# STM32-Mentor.net
KiCad netlist of a schematic drawn in Altium Designer
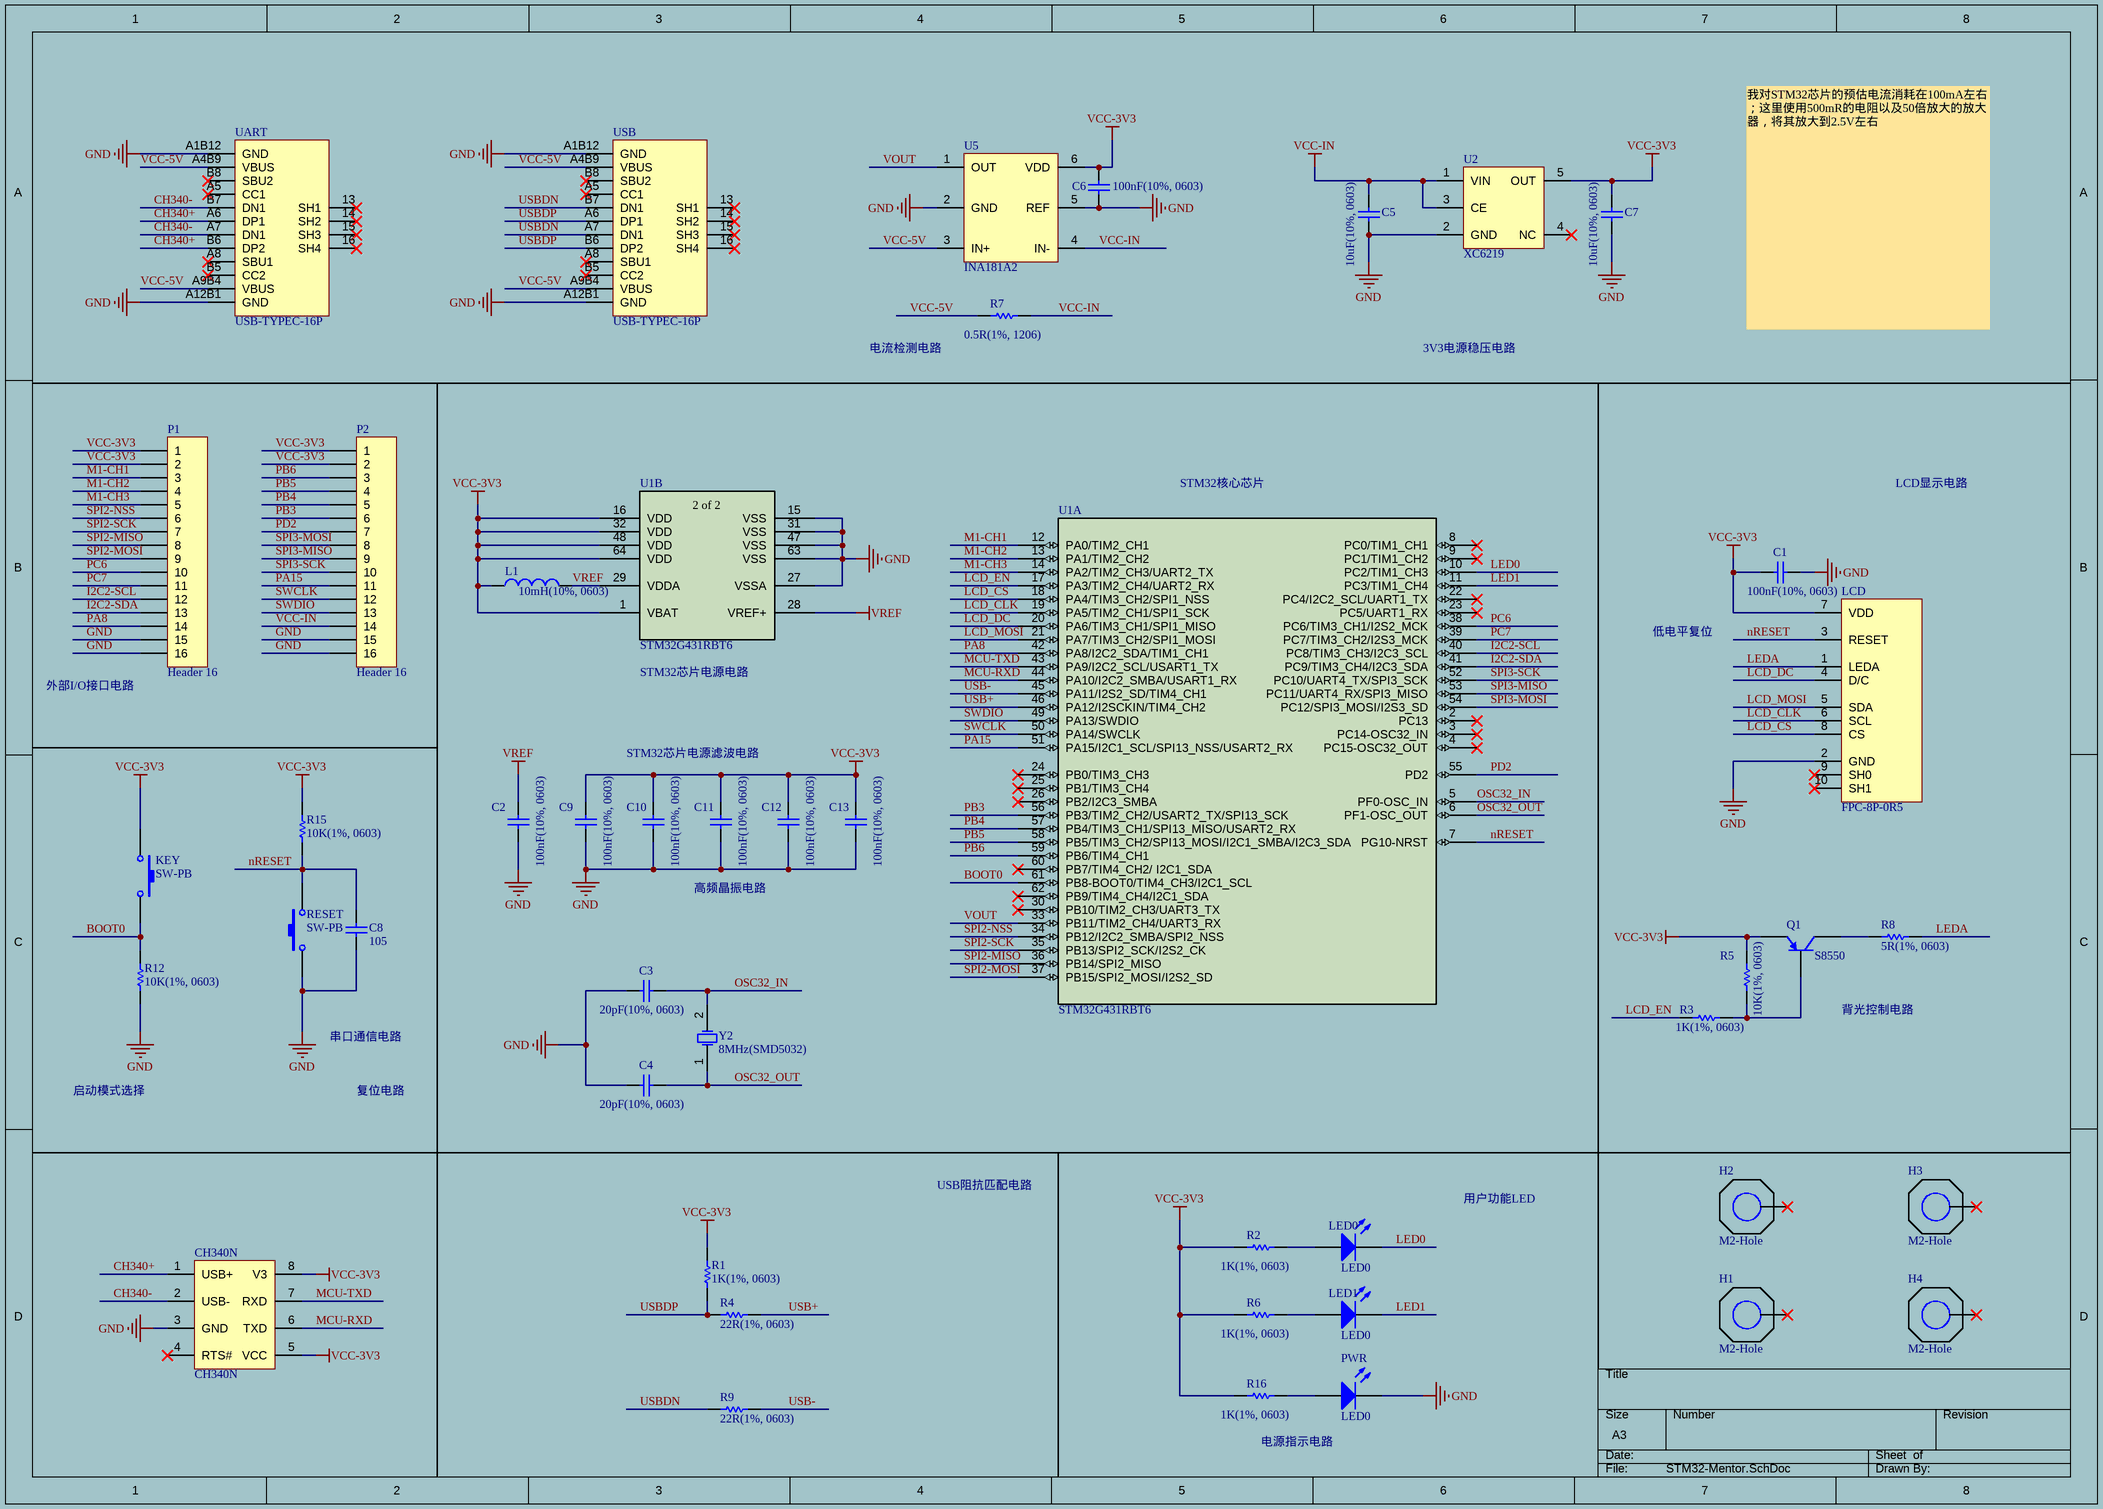
[diagram p0: STM32-Mentor.SchDoc]

(export (version "E")
  (design (tool "Eeschema 10.0.6"))
  (components
    (comp (ref "C1")
      (value "100nF(10%, 0603)")
      (footprint "0603C")
      (description "Capacitor")
      (fields (field (name "PUBLISHER") "Altium Limited"))
      (libsource (lib "Miscellaneous Devices") (part "Cap"))
    )
    (comp (ref "C2")
      (value "100nF(10%, 0603)")
      (footprint "0603C")
      (description "Capacitor")
      (fields (field (name "PUBLISHER") "Altium Limited"))
      (libsource (lib "Miscellaneous Devices") (part "Cap"))
    )
    (comp (ref "C3")
      (value "20pF(10%, 0603)")
      (footprint "0603C")
      (description "Capacitor")
      (fields (field (name "PUBLISHER") "Altium Limited"))
      (libsource (lib "Miscellaneous Devices") (part "Cap"))
    )
    (comp (ref "C4")
      (value "20pF(10%, 0603)")
      (footprint "0603C")
      (description "Capacitor")
      (fields (field (name "PUBLISHER") "Altium Limited"))
      (libsource (lib "Miscellaneous Devices") (part "Cap"))
    )
    (comp (ref "C5")
      (value "10uF(10%, 0603)")
      (footprint "0603C")
      (description "Capacitor")
      (fields (field (name "PUBLISHER") "Altium Limited"))
      (libsource (lib "Miscellaneous Devices") (part "Cap"))
    )
    (comp (ref "C6")
      (value "100nF(10%, 0603)")
      (footprint "0603C")
      (description "Capacitor")
      (fields (field (name "PUBLISHER") "Altium Limited"))
      (libsource (lib "Miscellaneous Devices") (part "Cap"))
    )
    (comp (ref "C7")
      (value "10uF(10%, 0603)")
      (footprint "0603C")
      (description "Capacitor")
      (fields (field (name "PUBLISHER") "Altium Limited"))
      (libsource (lib "Miscellaneous Devices") (part "Cap"))
    )
    (comp (ref "C8")
      (value "105")
      (footprint "0603C")
      (description "Capacitor")
      (fields (field (name "PUBLISHER") "Altium Limited"))
      (libsource (lib "Miscellaneous Devices") (part "Cap"))
    )
    (comp (ref "C9")
      (value "100nF(10%, 0603)")
      (footprint "0603C")
      (description "Capacitor")
      (fields (field (name "PUBLISHER") "Altium Limited"))
      (libsource (lib "Miscellaneous Devices") (part "Cap"))
    )
    (comp (ref "C10")
      (value "100nF(10%, 0603)")
      (footprint "0603C")
      (description "Capacitor")
      (fields (field (name "PUBLISHER") "Altium Limited"))
      (libsource (lib "Miscellaneous Devices") (part "Cap"))
    )
    (comp (ref "C11")
      (value "100nF(10%, 0603)")
      (footprint "0603C")
      (description "Capacitor")
      (fields (field (name "PUBLISHER") "Altium Limited"))
      (libsource (lib "Miscellaneous Devices") (part "Cap"))
    )
    (comp (ref "C12")
      (value "100nF(10%, 0603)")
      (footprint "0603C")
      (description "Capacitor")
      (fields (field (name "PUBLISHER") "Altium Limited"))
      (libsource (lib "Miscellaneous Devices") (part "Cap"))
    )
    (comp (ref "C13")
      (value "100nF(10%, 0603)")
      (footprint "0603C")
      (description "Capacitor")
      (fields (field (name "PUBLISHER") "Altium Limited"))
      (libsource (lib "Miscellaneous Devices") (part "Cap"))
    )
    (comp (ref "CH340N")
      (value "CH340N")
      (footprint "SOP8")
      (description "UART To USB")
      (libsource (lib "RegularLib") (part "CH340N"))
    )
    (comp (ref "H1") (value "M2-Hole") (footprint "M2-Hole") (libsource (lib "RegularLib") (part "M2-Hole")))
    (comp (ref "H2") (value "M2-Hole") (footprint "M2-Hole") (libsource (lib "RegularLib") (part "M2-Hole")))
    (comp (ref "H3") (value "M2-Hole") (footprint "M2-Hole") (libsource (lib "RegularLib") (part "M2-Hole")))
    (comp (ref "H4") (value "M2-Hole") (footprint "M2-Hole") (libsource (lib "RegularLib") (part "M2-Hole")))
    (comp (ref "KEY")
      (value "SW-PB")
      (footprint "SW2-4R2X3R4")
      (description "Switch")
      (fields (field (name "PUBLISHER") "Altium Limited"))
      (libsource (lib "Miscellaneous Devices") (part "SW-PB"))
    )
    (comp (ref "L1")
      (value "10mH(10%, 0603)")
      (footprint "0805L")
      (description "Inductor")
      (fields (field (name "PUBLISHER") "Altium Limited"))
      (libsource (lib "Miscellaneous Devices") (part "Inductor"))
    )
    (comp (ref "LCD")
      (value "FPC-8P-0R5")
      (footprint "FPC-8P-0R5")
      (libsource (lib "RegularLib") (part "FPC-8P-0R5"))
    )
    (comp (ref "LED0")
      (value "LED0")
      (footprint "LED-0805")
      (description "Typical INFRARED GaAs LED")
      (fields (field (name "PUBLISHER") "Altium Limited"))
      (libsource (lib "Miscellaneous Devices") (part "LED0"))
    )
    (comp (ref "LED1")
      (value "LED0")
      (footprint "LED-0805")
      (description "Typical INFRARED GaAs LED")
      (fields (field (name "PUBLISHER") "Altium Limited"))
      (libsource (lib "Miscellaneous Devices") (part "LED0"))
    )
    (comp (ref "P1")
      (value "Header 16")
      (footprint "HDR1X16")
      (description "Header, 16-Pin")
      (fields (field (name "PUBLISHER") "Altium Limited"))
      (libsource (lib "Miscellaneous Connectors") (part "Header 16"))
    )
    (comp (ref "P2")
      (value "Header 16")
      (footprint "HDR1X16")
      (description "Header, 16-Pin")
      (fields (field (name "PUBLISHER") "Altium Limited"))
      (libsource (lib "Miscellaneous Connectors") (part "Header 16"))
    )
    (comp (ref "PWR")
      (value "LED0")
      (footprint "LED-0805")
      (description "Typical INFRARED GaAs LED")
      (fields (field (name "PUBLISHER") "Altium Limited"))
      (libsource (lib "Miscellaneous Devices") (part "LED0"))
    )
    (comp (ref "Q1")
      (value "S8550")
      (footprint "SOT-23B_N")
      (description "PNP Bipolar Transistor")
      (fields (field (name "PUBLISHER") "Altium Limited"))
      (libsource (lib "Miscellaneous Devices") (part "PNP"))
    )
    (comp (ref "R1")
      (value "1K(1%, 0603)")
      (footprint "0603R")
      (description "Resistor")
      (fields (field (name "PUBLISHER") "Altium Limited"))
      (libsource (lib "Miscellaneous Devices") (part "Res1"))
    )
    (comp (ref "R2")
      (value "1K(1%, 0603)")
      (footprint "0603R")
      (description "Resistor")
      (fields (field (name "PUBLISHER") "Altium Limited"))
      (libsource (lib "Miscellaneous Devices") (part "Res1"))
    )
    (comp (ref "R3")
      (value "1K(1%, 0603)")
      (footprint "0603R")
      (description "Resistor")
      (fields (field (name "PUBLISHER") "Altium Limited"))
      (libsource (lib "Miscellaneous Devices") (part "Res1"))
    )
    (comp (ref "R4")
      (value "22R(1%, 0603)")
      (footprint "0603R")
      (description "Resistor")
      (fields (field (name "PUBLISHER") "Altium Limited"))
      (libsource (lib "Miscellaneous Devices") (part "Res1"))
    )
    (comp (ref "R5")
      (value "10K(1%, 0603)")
      (footprint "0603R")
      (description "Resistor")
      (fields (field (name "PUBLISHER") "Altium Limited"))
      (libsource (lib "Miscellaneous Devices") (part "Res1"))
    )
    (comp (ref "R6")
      (value "1K(1%, 0603)")
      (footprint "0603R")
      (description "Resistor")
      (fields (field (name "PUBLISHER") "Altium Limited"))
      (libsource (lib "Miscellaneous Devices") (part "Res1"))
    )
    (comp (ref "R7")
      (value "0.5R(1%, 1206)")
      (footprint "1206R")
      (description "Resistor")
      (fields (field (name "PUBLISHER") "Altium Limited"))
      (libsource (lib "Miscellaneous Devices") (part "Res1"))
    )
    (comp (ref "R8")
      (value "5R(1%, 0603)")
      (footprint "0603R")
      (description "Resistor")
      (fields (field (name "PUBLISHER") "Altium Limited"))
      (libsource (lib "Miscellaneous Devices") (part "Res1"))
    )
    (comp (ref "R9")
      (value "22R(1%, 0603)")
      (footprint "0603R")
      (description "Resistor")
      (fields (field (name "PUBLISHER") "Altium Limited"))
      (libsource (lib "Miscellaneous Devices") (part "Res1"))
    )
    (comp (ref "R12")
      (value "10K(1%, 0603)")
      (footprint "0603R")
      (description "Resistor")
      (fields (field (name "PUBLISHER") "Altium Limited"))
      (libsource (lib "Miscellaneous Devices") (part "Res1"))
    )
    (comp (ref "R15")
      (value "10K(1%, 0603)")
      (footprint "0603R")
      (description "Resistor")
      (fields (field (name "PUBLISHER") "Altium Limited"))
      (libsource (lib "Miscellaneous Devices") (part "Res1"))
    )
    (comp (ref "R16")
      (value "1K(1%, 0603)")
      (footprint "0603R")
      (description "Resistor")
      (fields (field (name "PUBLISHER") "Altium Limited"))
      (libsource (lib "Miscellaneous Devices") (part "Res1"))
    )
    (comp (ref "RESET")
      (value "SW-PB")
      (footprint "SW2-4R2X3R4")
      (description "Switch")
      (fields (field (name "PUBLISHER") "Altium Limited"))
      (libsource (lib "Miscellaneous Devices") (part "SW-PB"))
    )
    (comp (ref "U1")
      (value "STM32G431RBT6")
      (footprint "LQFP64-10x10mm")
      (description "No Description Available")
      (fields (field (name "COPYRIGHT") "Copyright (C) 2024 Ultra Librarian. All rights reserved."))
      (libsource (lib "STM32G431RBT6") (part "STM32G431RBT6"))
    )
    (comp (ref "U2")
      (value "XC6219")
      (footprint "SOT23-5")
      (description "POWER: LDO regulator for 3V3")
      (libsource (lib "RegularLib") (part "XC6219"))
    )
    (comp (ref "U5")
      (value "INA181A2")
      (footprint "SOT23-6")
      (description "Amp: current amplifire")
      (libsource (lib "RegularLib") (part "INA181A2"))
    )
    (comp (ref "UART")
      (value "USB-TYPEC-16P")
      (footprint "USB-TYPEC-16P")
      (libsource (lib "RegularLib") (part "USB-TYPEC-16P"))
    )
    (comp (ref "USB")
      (value "USB-TYPEC-16P")
      (footprint "USB-TYPEC-16P")
      (libsource (lib "RegularLib") (part "USB-TYPEC-16P"))
    )
    (comp (ref "Y2")
      (value "8MHz(SMD5032)")
      (footprint "SMD5032-2P")
      (description "Crystal Oscillator")
      (fields (field (name "PUBLISHER") "Altium Limited"))
      (libsource (lib "Miscellaneous Devices") (part "XTAL"))
    )
  )
  (nets
    (net (code "1") (name "/BOOT0") (class "Default")
      (node (ref "KEY") (pin "2") (pinfunction "2_2") (pintype "passive"))
      (node (ref "R12") (pin "2") (pinfunction "2_2") (pintype "passive"))
      (node (ref "U1") (pin "61") (pinfunction "PB8-BOOT0/TIM4_CH3/I2C1_SCL_61") (pintype "bidirectional"))
    )
    (net (code "2") (name "/CH340+") (class "Default")
      (node (ref "CH340N") (pin "1") (pinfunction "USB+_1") (pintype "passive"))
      (node (ref "UART") (pin "A6") (pinfunction "DP1_A6") (pintype "passive"))
      (node (ref "UART") (pin "B6") (pinfunction "DP2_B6") (pintype "passive"))
    )
    (net (code "3") (name "/CH340-") (class "Default")
      (node (ref "CH340N") (pin "2") (pinfunction "USB-_2") (pintype "passive"))
      (node (ref "UART") (pin "A7") (pinfunction "DN1_A7") (pintype "passive"))
      (node (ref "UART") (pin "B7") (pinfunction "DN1_B7") (pintype "passive"))
    )
    (net (code "4") (name "/I2C2-SCL") (class "Default")
      (node (ref "P1") (pin "12") (pinfunction "12_12") (pintype "passive"))
      (node (ref "U1") (pin "40") (pinfunction "PC8/TIM3_CH3/I2C3_SCL_40") (pintype "bidirectional"))
    )
    (net (code "5") (name "/I2C2-SDA") (class "Default")
      (node (ref "P1") (pin "13") (pinfunction "13_13") (pintype "passive"))
      (node (ref "U1") (pin "41") (pinfunction "PC9/TIM3_CH4/I2C3_SDA_41") (pintype "bidirectional"))
    )
    (net (code "6") (name "/LCD_CLK") (class "Default")
      (node (ref "LCD") (pin "6") (pinfunction "SCL_6") (pintype "passive"))
      (node (ref "U1") (pin "19") (pinfunction "PA5/TIM2_CH1/SPI1_SCK_19") (pintype "bidirectional"))
    )
    (net (code "7") (name "/LCD_CS") (class "Default")
      (node (ref "LCD") (pin "8") (pinfunction "CS_8") (pintype "passive"))
      (node (ref "U1") (pin "18") (pinfunction "PA4/TIM3_CH2/SPI1_NSS_18") (pintype "bidirectional"))
    )
    (net (code "8") (name "/LCD_DC") (class "Default")
      (node (ref "LCD") (pin "4") (pinfunction "D/C_4") (pintype "passive"))
      (node (ref "U1") (pin "20") (pinfunction "PA6/TIM3_CH1/SPI1_MISO_20") (pintype "bidirectional"))
    )
    (net (code "9") (name "/LCD_EN") (class "Default")
      (node (ref "R3") (pin "1") (pinfunction "1_1") (pintype "passive"))
      (node (ref "U1") (pin "17") (pinfunction "PA3/TIM2_CH4/UART2_RX_17") (pintype "bidirectional"))
    )
    (net (code "10") (name "/LCD_MOSI") (class "Default")
      (node (ref "LCD") (pin "5") (pinfunction "SDA_5") (pintype "passive"))
      (node (ref "U1") (pin "21") (pinfunction "PA7/TIM3_CH2/SPI1_MOSI_21") (pintype "bidirectional"))
    )
    (net (code "11") (name "/LED0") (class "Default")
      (node (ref "LED0") (pin "2") (pinfunction "K_2") (pintype "passive"))
      (node (ref "U1") (pin "10") (pinfunction "PC2/TIM1_CH3_10") (pintype "bidirectional"))
    )
    (net (code "12") (name "/LED1") (class "Default")
      (node (ref "LED1") (pin "2") (pinfunction "K_2") (pintype "passive"))
      (node (ref "U1") (pin "11") (pinfunction "PC3/TIM1_CH4_11") (pintype "bidirectional"))
    )
    (net (code "13") (name "/LEDA") (class "Default")
      (node (ref "LCD") (pin "1") (pinfunction "LEDA_1") (pintype "passive"))
      (node (ref "R8") (pin "2") (pinfunction "2_2") (pintype "passive"))
    )
    (net (code "14") (name "/M1-CH1") (class "Default")
      (node (ref "P1") (pin "3") (pinfunction "3_3") (pintype "passive"))
      (node (ref "U1") (pin "12") (pinfunction "PA0/TIM2_CH1_12") (pintype "bidirectional"))
    )
    (net (code "15") (name "/M1-CH2") (class "Default")
      (node (ref "P1") (pin "4") (pinfunction "4_4") (pintype "passive"))
      (node (ref "U1") (pin "13") (pinfunction "PA1/TIM2_CH2_13") (pintype "bidirectional"))
    )
    (net (code "16") (name "/M1-CH3") (class "Default")
      (node (ref "P1") (pin "5") (pinfunction "5_5") (pintype "passive"))
      (node (ref "U1") (pin "14") (pinfunction "PA2/TIM2_CH3/UART2_TX_14") (pintype "bidirectional"))
    )
    (net (code "17") (name "/MCU-RXD") (class "Default")
      (node (ref "CH340N") (pin "6") (pinfunction "TXD_6") (pintype "passive"))
      (node (ref "U1") (pin "44") (pinfunction "PA10/I2C2_SMBA/USART1_RX_44") (pintype "bidirectional"))
    )
    (net (code "18") (name "/MCU-TXD") (class "Default")
      (node (ref "CH340N") (pin "7") (pinfunction "RXD_7") (pintype "passive"))
      (node (ref "U1") (pin "43") (pinfunction "PA9/I2C2_SCL/USART1_TX_43") (pintype "bidirectional"))
    )
    (net (code "19") (name "/OSC32_IN") (class "Default")
      (node (ref "C3") (pin "2") (pinfunction "2_2") (pintype "passive"))
      (node (ref "U1") (pin "5") (pinfunction "PF0-OSC_IN_5") (pintype "bidirectional"))
      (node (ref "Y2") (pin "2") (pinfunction "OSC2_2") (pintype "passive"))
    )
    (net (code "20") (name "/OSC32_OUT") (class "Default")
      (node (ref "C4") (pin "2") (pinfunction "2_2") (pintype "passive"))
      (node (ref "U1") (pin "6") (pinfunction "PF1-OSC_OUT_6") (pintype "bidirectional"))
      (node (ref "Y2") (pin "1") (pinfunction "OSC1_1") (pintype "passive"))
    )
    (net (code "21") (name "/PA8") (class "Default")
      (node (ref "P1") (pin "14") (pinfunction "14_14") (pintype "passive"))
      (node (ref "U1") (pin "42") (pinfunction "PA8/I2C2_SDA/TIM1_CH1_42") (pintype "bidirectional"))
    )
    (net (code "22") (name "/PA15") (class "Default")
      (node (ref "P2") (pin "11") (pinfunction "11_11") (pintype "passive"))
      (node (ref "U1") (pin "51") (pinfunction "PA15/I2C1_SCL/SPI13_NSS/USART2_RX_51") (pintype "bidirectional"))
    )
    (net (code "23") (name "/PB3") (class "Default")
      (node (ref "P2") (pin "6") (pinfunction "6_6") (pintype "passive"))
      (node (ref "U1") (pin "56") (pinfunction "PB3/TIM2_CH2/USART2_TX/SPI13_SCK_56") (pintype "bidirectional"))
    )
    (net (code "24") (name "/PB4") (class "Default")
      (node (ref "P2") (pin "5") (pinfunction "5_5") (pintype "passive"))
      (node (ref "U1") (pin "57") (pinfunction "PB4/TIM3_CH1/SPI13_MISO/USART2_RX_57") (pintype "bidirectional"))
    )
    (net (code "25") (name "/PB5") (class "Default")
      (node (ref "P2") (pin "4") (pinfunction "4_4") (pintype "passive"))
      (node (ref "U1") (pin "58") (pinfunction "PB5/TIM3_CH2/SPI13_MOSI/I2C1_SMBA/I2C3_SDA_58") (pintype "bidirectional"))
    )
    (net (code "26") (name "/PB6") (class "Default")
      (node (ref "P2") (pin "3") (pinfunction "3_3") (pintype "passive"))
      (node (ref "U1") (pin "59") (pinfunction "PB6/TIM4_CH1_59") (pintype "bidirectional"))
    )
    (net (code "27") (name "/PC6") (class "Default")
      (node (ref "P1") (pin "10") (pinfunction "10_10") (pintype "passive"))
      (node (ref "U1") (pin "38") (pinfunction "PC6/TIM3_CH1/I2S2_MCK_38") (pintype "bidirectional"))
    )
    (net (code "28") (name "/PC7") (class "Default")
      (node (ref "P1") (pin "11") (pinfunction "11_11") (pintype "passive"))
      (node (ref "U1") (pin "39") (pinfunction "PC7/TIM3_CH2/I2S3_MCK_39") (pintype "bidirectional"))
    )
    (net (code "29") (name "/PD2") (class "Default")
      (node (ref "P2") (pin "7") (pinfunction "7_7") (pintype "passive"))
      (node (ref "U1") (pin "55") (pinfunction "PD2_55") (pintype "bidirectional"))
    )
    (net (code "30") (name "/SPI2-MISO") (class "Default")
      (node (ref "P1") (pin "8") (pinfunction "8_8") (pintype "passive"))
      (node (ref "U1") (pin "36") (pinfunction "PB14/SPI2_MISO_36") (pintype "bidirectional"))
    )
    (net (code "31") (name "/SPI2-MOSI") (class "Default")
      (node (ref "P1") (pin "9") (pinfunction "9_9") (pintype "passive"))
      (node (ref "U1") (pin "37") (pinfunction "PB15/SPI2_MOSI/I2S2_SD_37") (pintype "bidirectional"))
    )
    (net (code "32") (name "/SPI2-NSS") (class "Default")
      (node (ref "P1") (pin "6") (pinfunction "6_6") (pintype "passive"))
      (node (ref "U1") (pin "34") (pinfunction "PB12/I2C2_SMBA/SPI2_NSS_34") (pintype "bidirectional"))
    )
    (net (code "33") (name "/SPI2-SCK") (class "Default")
      (node (ref "P1") (pin "7") (pinfunction "7_7") (pintype "passive"))
      (node (ref "U1") (pin "35") (pinfunction "PB13/SPI2_SCK/I2S2_CK_35") (pintype "bidirectional"))
    )
    (net (code "34") (name "/SPI3-MISO") (class "Default")
      (node (ref "P2") (pin "9") (pinfunction "9_9") (pintype "passive"))
      (node (ref "U1") (pin "53") (pinfunction "PC11/UART4_RX/SPI3_MISO_53") (pintype "bidirectional"))
    )
    (net (code "35") (name "/SPI3-MOSI") (class "Default")
      (node (ref "P2") (pin "8") (pinfunction "8_8") (pintype "passive"))
      (node (ref "U1") (pin "54") (pinfunction "PC12/SPI3_MOSI/I2S3_SD_54") (pintype "bidirectional"))
    )
    (net (code "36") (name "/SPI3-SCK") (class "Default")
      (node (ref "P2") (pin "10") (pinfunction "10_10") (pintype "passive"))
      (node (ref "U1") (pin "52") (pinfunction "PC10/UART4_TX/SPI3_SCK_52") (pintype "bidirectional"))
    )
    (net (code "37") (name "/SWCLK") (class "Default")
      (node (ref "P2") (pin "12") (pinfunction "12_12") (pintype "passive"))
      (node (ref "U1") (pin "50") (pinfunction "PA14/SWCLK_50") (pintype "bidirectional"))
    )
    (net (code "38") (name "/SWDIO") (class "Default")
      (node (ref "P2") (pin "13") (pinfunction "13_13") (pintype "passive"))
      (node (ref "U1") (pin "49") (pinfunction "PA13/SWDIO_49") (pintype "bidirectional"))
    )
    (net (code "39") (name "/USB+") (class "Default")
      (node (ref "R4") (pin "2") (pinfunction "2_2") (pintype "passive"))
      (node (ref "U1") (pin "46") (pinfunction "PA12/I2SCKIN/TIM4_CH2_46") (pintype "bidirectional"))
    )
    (net (code "40") (name "/USB-") (class "Default")
      (node (ref "R9") (pin "2") (pinfunction "2_2") (pintype "passive"))
      (node (ref "U1") (pin "45") (pinfunction "PA11/I2S2_SD/TIM4_CH1_45") (pintype "bidirectional"))
    )
    (net (code "41") (name "/USBDN") (class "Default")
      (node (ref "R9") (pin "1") (pinfunction "1_1") (pintype "passive"))
      (node (ref "USB") (pin "A7") (pinfunction "DN1_A7") (pintype "passive"))
      (node (ref "USB") (pin "B7") (pinfunction "DN1_B7") (pintype "passive"))
    )
    (net (code "42") (name "/USBDP") (class "Default")
      (node (ref "R1") (pin "1") (pinfunction "1_1") (pintype "passive"))
      (node (ref "R4") (pin "1") (pinfunction "1_1") (pintype "passive"))
      (node (ref "USB") (pin "A6") (pinfunction "DP1_A6") (pintype "passive"))
      (node (ref "USB") (pin "B6") (pinfunction "DP2_B6") (pintype "passive"))
    )
    (net (code "43") (name "/VCC-5V") (class "Default")
      (node (ref "R7") (pin "1") (pinfunction "1_1") (pintype "passive"))
      (node (ref "U5") (pin "3") (pinfunction "IN+_3") (pintype "passive"))
      (node (ref "UART") (pin "A4B9") (pinfunction "VBUS_A4B9") (pintype "passive"))
      (node (ref "UART") (pin "A9B4") (pinfunction "VBUS_A9B4") (pintype "passive"))
      (node (ref "USB") (pin "A4B9") (pinfunction "VBUS_A4B9") (pintype "passive"))
      (node (ref "USB") (pin "A9B4") (pinfunction "VBUS_A9B4") (pintype "passive"))
    )
    (net (code "44") (name "/VOUT") (class "Default")
      (node (ref "U1") (pin "33") (pinfunction "PB11/TIM2_CH4/UART3_RX_33") (pintype "bidirectional"))
      (node (ref "U5") (pin "1") (pinfunction "OUT_1") (pintype "passive"))
    )
    (net (code "45") (name "/nRESET") (class "Default")
      (node (ref "C8") (pin "2") (pinfunction "2_2") (pintype "passive"))
      (node (ref "LCD") (pin "3") (pinfunction "RESET_3") (pintype "passive"))
      (node (ref "R15") (pin "1") (pinfunction "1_1") (pintype "passive"))
      (node (ref "RESET") (pin "2") (pinfunction "2_2") (pintype "passive"))
      (node (ref "U1") (pin "7") (pinfunction "PG10-NRST_7") (pintype "bidirectional"))
    )
    (net (code "46") (name "GND") (class "Default")
      (node (ref "C1") (pin "2") (pinfunction "2_2") (pintype "passive"))
      (node (ref "C10") (pin "1") (pinfunction "1_1") (pintype "passive"))
      (node (ref "C11") (pin "1") (pinfunction "1_1") (pintype "passive"))
      (node (ref "C12") (pin "1") (pinfunction "1_1") (pintype "passive"))
      (node (ref "C13") (pin "1") (pinfunction "1_1") (pintype "passive"))
      (node (ref "C2") (pin "1") (pinfunction "1_1") (pintype "passive"))
      (node (ref "C3") (pin "1") (pinfunction "1_1") (pintype "passive"))
      (node (ref "C4") (pin "1") (pinfunction "1_1") (pintype "passive"))
      (node (ref "C5") (pin "1") (pinfunction "1_1") (pintype "passive"))
      (node (ref "C6") (pin "1") (pinfunction "1_1") (pintype "passive"))
      (node (ref "C7") (pin "1") (pinfunction "1_1") (pintype "passive"))
      (node (ref "C8") (pin "1") (pinfunction "1_1") (pintype "passive"))
      (node (ref "C9") (pin "1") (pinfunction "1_1") (pintype "passive"))
      (node (ref "CH340N") (pin "3") (pinfunction "GND_3") (pintype "passive"))
      (node (ref "LCD") (pin "2") (pinfunction "GND_2") (pintype "passive"))
      (node (ref "P1") (pin "15") (pinfunction "15_15") (pintype "passive"))
      (node (ref "P1") (pin "16") (pinfunction "16_16") (pintype "passive"))
      (node (ref "P2") (pin "15") (pinfunction "15_15") (pintype "passive"))
      (node (ref "P2") (pin "16") (pinfunction "16_16") (pintype "passive"))
      (node (ref "PWR") (pin "2") (pinfunction "K_2") (pintype "passive"))
      (node (ref "R12") (pin "1") (pinfunction "1_1") (pintype "passive"))
      (node (ref "RESET") (pin "1") (pinfunction "1_1") (pintype "passive"))
      (node (ref "U1") (pin "15") (pinfunction "VSS_15") (pintype "power_in"))
      (node (ref "U1") (pin "27") (pinfunction "VSSA_27") (pintype "power_in"))
      (node (ref "U1") (pin "31") (pinfunction "VSS_31") (pintype "power_in"))
      (node (ref "U1") (pin "47") (pinfunction "VSS_47") (pintype "power_in"))
      (node (ref "U1") (pin "63") (pinfunction "VSS_63") (pintype "power_in"))
      (node (ref "U2") (pin "2") (pinfunction "GND_2") (pintype "passive"))
      (node (ref "U5") (pin "2") (pinfunction "GND_2") (pintype "passive"))
      (node (ref "U5") (pin "5") (pinfunction "REF_5") (pintype "passive"))
      (node (ref "UART") (pin "A12B1") (pinfunction "GND_A12B1") (pintype "passive"))
      (node (ref "UART") (pin "A1B12") (pinfunction "GND_A1B12") (pintype "passive"))
      (node (ref "USB") (pin "A12B1") (pinfunction "GND_A12B1") (pintype "passive"))
      (node (ref "USB") (pin "A1B12") (pinfunction "GND_A1B12") (pintype "passive"))
    )
    (net (code "47") (name "Net-(LED0-A)") (class "Default")
      (node (ref "LED0") (pin "1") (pinfunction "A_1") (pintype "passive"))
      (node (ref "R2") (pin "2") (pinfunction "2_2") (pintype "passive"))
    )
    (net (code "48") (name "Net-(LED1-A)") (class "Default")
      (node (ref "LED1") (pin "1") (pinfunction "A_1") (pintype "passive"))
      (node (ref "R6") (pin "2") (pinfunction "2_2") (pintype "passive"))
    )
    (net (code "49") (name "Net-(PWR-A)") (class "Default")
      (node (ref "PWR") (pin "1") (pinfunction "A_1") (pintype "passive"))
      (node (ref "R16") (pin "1") (pinfunction "1_1") (pintype "passive"))
    )
    (net (code "50") (name "Net-(Q1-B)") (class "Default")
      (node (ref "Q1") (pin "2") (pinfunction "B_2") (pintype "passive"))
      (node (ref "R3") (pin "2") (pinfunction "2_2") (pintype "passive"))
      (node (ref "R5") (pin "2") (pinfunction "2_2") (pintype "passive"))
    )
    (net (code "51") (name "Net-(Q1-C)") (class "Default")
      (node (ref "Q1") (pin "1") (pinfunction "C_1") (pintype "passive"))
      (node (ref "R8") (pin "1") (pinfunction "1_1") (pintype "passive"))
    )
    (net (code "52") (name "VCC-3V3") (class "Default")
      (node (ref "C1") (pin "1") (pinfunction "1_1") (pintype "passive"))
      (node (ref "C10") (pin "2") (pinfunction "2_2") (pintype "passive"))
      (node (ref "C11") (pin "2") (pinfunction "2_2") (pintype "passive"))
      (node (ref "C12") (pin "2") (pinfunction "2_2") (pintype "passive"))
      (node (ref "C13") (pin "2") (pinfunction "2_2") (pintype "passive"))
      (node (ref "C6") (pin "2") (pinfunction "2_2") (pintype "passive"))
      (node (ref "C7") (pin "2") (pinfunction "2_2") (pintype "passive"))
      (node (ref "C9") (pin "2") (pinfunction "2_2") (pintype "passive"))
      (node (ref "CH340N") (pin "5") (pinfunction "VCC_5") (pintype "passive"))
      (node (ref "CH340N") (pin "8") (pinfunction "V3_8") (pintype "passive"))
      (node (ref "KEY") (pin "1") (pinfunction "1_1") (pintype "passive"))
      (node (ref "L1") (pin "1") (pinfunction "1_1") (pintype "passive"))
      (node (ref "LCD") (pin "7") (pinfunction "VDD_7") (pintype "passive"))
      (node (ref "P1") (pin "1") (pinfunction "1_1") (pintype "passive"))
      (node (ref "P1") (pin "2") (pinfunction "2_2") (pintype "passive"))
      (node (ref "P2") (pin "1") (pinfunction "1_1") (pintype "passive"))
      (node (ref "P2") (pin "2") (pinfunction "2_2") (pintype "passive"))
      (node (ref "Q1") (pin "3") (pinfunction "E_3") (pintype "passive"))
      (node (ref "R1") (pin "2") (pinfunction "2_2") (pintype "passive"))
      (node (ref "R15") (pin "2") (pinfunction "2_2") (pintype "passive"))
      (node (ref "R16") (pin "2") (pinfunction "2_2") (pintype "passive"))
      (node (ref "R2") (pin "1") (pinfunction "1_1") (pintype "passive"))
      (node (ref "R5") (pin "1") (pinfunction "1_1") (pintype "passive"))
      (node (ref "R6") (pin "1") (pinfunction "1_1") (pintype "passive"))
      (node (ref "U1") (pin "1") (pinfunction "VBAT_1") (pintype "power_in"))
      (node (ref "U1") (pin "16") (pinfunction "VDD_16") (pintype "power_in"))
      (node (ref "U1") (pin "32") (pinfunction "VDD_32") (pintype "power_in"))
      (node (ref "U1") (pin "48") (pinfunction "VDD_48") (pintype "power_in"))
      (node (ref "U1") (pin "64") (pinfunction "VDD_64") (pintype "power_in"))
      (node (ref "U2") (pin "5") (pinfunction "OUT_5") (pintype "passive"))
      (node (ref "U5") (pin "6") (pinfunction "VDD_6") (pintype "passive"))
    )
    (net (code "53") (name "VCC-IN") (class "Default")
      (node (ref "C5") (pin "2") (pinfunction "2_2") (pintype "passive"))
      (node (ref "P2") (pin "14") (pinfunction "14_14") (pintype "passive"))
      (node (ref "R7") (pin "2") (pinfunction "2_2") (pintype "passive"))
      (node (ref "U2") (pin "1") (pinfunction "VIN_1") (pintype "passive"))
      (node (ref "U2") (pin "3") (pinfunction "CE_3") (pintype "passive"))
      (node (ref "U5") (pin "4") (pinfunction "IN-_4") (pintype "passive"))
    )
    (net (code "54") (name "VREF") (class "Default")
      (node (ref "C2") (pin "2") (pinfunction "2_2") (pintype "passive"))
      (node (ref "L1") (pin "2") (pinfunction "2_2") (pintype "passive"))
      (node (ref "U1") (pin "28") (pinfunction "VREF+_28") (pintype "power_in"))
      (node (ref "U1") (pin "29") (pinfunction "VDDA_29") (pintype "power_in"))
    )
    (net (code "55") (name "unconnected-(CH340N-RTS#-Pad4)") (class "Default")
      (node (ref "CH340N") (pin "4") (pinfunction "RTS#_4") (pintype "passive+no_connect"))
    )
    (net (code "56") (name "unconnected-(H1-5-Pad0)") (class "Default")
      (node (ref "H1") (pin "0") (pinfunction "5_0") (pintype "passive+no_connect"))
    )
    (net (code "57") (name "unconnected-(H2-5-Pad0)") (class "Default")
      (node (ref "H2") (pin "0") (pinfunction "5_0") (pintype "passive+no_connect"))
    )
    (net (code "58") (name "unconnected-(H3-5-Pad0)") (class "Default")
      (node (ref "H3") (pin "0") (pinfunction "5_0") (pintype "passive+no_connect"))
    )
    (net (code "59") (name "unconnected-(H4-5-Pad0)") (class "Default")
      (node (ref "H4") (pin "0") (pinfunction "5_0") (pintype "passive+no_connect"))
    )
    (net (code "60") (name "unconnected-(LCD-SH0-Pad9)") (class "Default")
      (node (ref "LCD") (pin "9") (pinfunction "SH0_9") (pintype "passive+no_connect"))
    )
    (net (code "61") (name "unconnected-(LCD-SH1-Pad10)") (class "Default")
      (node (ref "LCD") (pin "10") (pinfunction "SH1_10") (pintype "passive+no_connect"))
    )
    (net (code "62") (name "unconnected-(U1A-PB0{slash}TIM3_CH3-Pad24)") (class "Default")
      (node (ref "U1") (pin "24") (pinfunction "PB0/TIM3_CH3_24") (pintype "bidirectional+no_connect"))
    )
    (net (code "63") (name "unconnected-(U1A-PB1{slash}TIM3_CH4-Pad25)") (class "Default")
      (node (ref "U1") (pin "25") (pinfunction "PB1/TIM3_CH4_25") (pintype "bidirectional+no_connect"))
    )
    (net (code "64") (name "unconnected-(U1A-PB2{slash}I2C3_SMBA-Pad26)") (class "Default")
      (node (ref "U1") (pin "26") (pinfunction "PB2/I2C3_SMBA_26") (pintype "bidirectional+no_connect"))
    )
    (net (code "65") (name "unconnected-(U1A-PB7{slash}TIM4_CH2{slash}_I2C1_SDA-Pad60)") (class "Default")
      (node (ref "U1") (pin "60") (pinfunction "PB7/TIM4_CH2/_I2C1_SDA_60") (pintype "bidirectional+no_connect"))
    )
    (net (code "66") (name "unconnected-(U1A-PB9{slash}TIM4_CH4{slash}I2C1_SDA-Pad62)") (class "Default")
      (node (ref "U1") (pin "62") (pinfunction "PB9/TIM4_CH4/I2C1_SDA_62") (pintype "bidirectional+no_connect"))
    )
    (net (code "67") (name "unconnected-(U1A-PB10{slash}TIM2_CH3{slash}UART3_TX-Pad30)") (class "Default")
      (node (ref "U1") (pin "30") (pinfunction "PB10/TIM2_CH3/UART3_TX_30") (pintype "bidirectional+no_connect"))
    )
    (net (code "68") (name "unconnected-(U1A-PC0{slash}TIM1_CH1-Pad8)") (class "Default")
      (node (ref "U1") (pin "8") (pinfunction "PC0/TIM1_CH1_8") (pintype "bidirectional+no_connect"))
    )
    (net (code "69") (name "unconnected-(U1A-PC1{slash}TIM1_CH2-Pad9)") (class "Default")
      (node (ref "U1") (pin "9") (pinfunction "PC1/TIM1_CH2_9") (pintype "bidirectional+no_connect"))
    )
    (net (code "70") (name "unconnected-(U1A-PC4{slash}I2C2_SCL{slash}UART1_TX-Pad22)") (class "Default")
      (node (ref "U1") (pin "22") (pinfunction "PC4/I2C2_SCL/UART1_TX_22") (pintype "bidirectional+no_connect"))
    )
    (net (code "71") (name "unconnected-(U1A-PC5{slash}UART1_RX-Pad23)") (class "Default")
      (node (ref "U1") (pin "23") (pinfunction "PC5/UART1_RX_23") (pintype "bidirectional+no_connect"))
    )
    (net (code "72") (name "unconnected-(U1A-PC13-Pad2)") (class "Default")
      (node (ref "U1") (pin "2") (pinfunction "PC13_2") (pintype "bidirectional+no_connect"))
    )
    (net (code "73") (name "unconnected-(U1A-PC14-OSC32_IN-Pad3)") (class "Default")
      (node (ref "U1") (pin "3") (pinfunction "PC14-OSC32_IN_3") (pintype "bidirectional+no_connect"))
    )
    (net (code "74") (name "unconnected-(U1A-PC15-OSC32_OUT-Pad4)") (class "Default")
      (node (ref "U1") (pin "4") (pinfunction "PC15-OSC32_OUT_4") (pintype "bidirectional+no_connect"))
    )
    (net (code "75") (name "unconnected-(U2-NC-Pad4)") (class "Default")
      (node (ref "U2") (pin "4") (pinfunction "NC_4") (pintype "passive+no_connect"))
    )
    (net (code "76") (name "unconnected-(UART-CC1-PadA5)") (class "Default")
      (node (ref "UART") (pin "A5") (pinfunction "CC1_A5") (pintype "passive+no_connect"))
    )
    (net (code "77") (name "unconnected-(UART-CC2-PadB5)") (class "Default")
      (node (ref "UART") (pin "B5") (pinfunction "CC2_B5") (pintype "passive+no_connect"))
    )
    (net (code "78") (name "unconnected-(UART-SBU1-PadA8)") (class "Default")
      (node (ref "UART") (pin "A8") (pinfunction "SBU1_A8") (pintype "passive+no_connect"))
    )
    (net (code "79") (name "unconnected-(UART-SBU2-PadB8)") (class "Default")
      (node (ref "UART") (pin "B8") (pinfunction "SBU2_B8") (pintype "passive+no_connect"))
    )
    (net (code "80") (name "unconnected-(UART-SH1-Pad13)") (class "Default")
      (node (ref "UART") (pin "13") (pinfunction "SH1_13") (pintype "passive+no_connect"))
    )
    (net (code "81") (name "unconnected-(UART-SH2-Pad14)") (class "Default")
      (node (ref "UART") (pin "14") (pinfunction "SH2_14") (pintype "passive+no_connect"))
    )
    (net (code "82") (name "unconnected-(UART-SH3-Pad15)") (class "Default")
      (node (ref "UART") (pin "15") (pinfunction "SH3_15") (pintype "passive+no_connect"))
    )
    (net (code "83") (name "unconnected-(UART-SH4-Pad16)") (class "Default")
      (node (ref "UART") (pin "16") (pinfunction "SH4_16") (pintype "passive+no_connect"))
    )
    (net (code "84") (name "unconnected-(USB-CC1-PadA5)") (class "Default")
      (node (ref "USB") (pin "A5") (pinfunction "CC1_A5") (pintype "passive+no_connect"))
    )
    (net (code "85") (name "unconnected-(USB-CC2-PadB5)") (class "Default")
      (node (ref "USB") (pin "B5") (pinfunction "CC2_B5") (pintype "passive+no_connect"))
    )
    (net (code "86") (name "unconnected-(USB-SBU1-PadA8)") (class "Default")
      (node (ref "USB") (pin "A8") (pinfunction "SBU1_A8") (pintype "passive+no_connect"))
    )
    (net (code "87") (name "unconnected-(USB-SBU2-PadB8)") (class "Default")
      (node (ref "USB") (pin "B8") (pinfunction "SBU2_B8") (pintype "passive+no_connect"))
    )
    (net (code "88") (name "unconnected-(USB-SH1-Pad13)") (class "Default")
      (node (ref "USB") (pin "13") (pinfunction "SH1_13") (pintype "passive+no_connect"))
    )
    (net (code "89") (name "unconnected-(USB-SH2-Pad14)") (class "Default")
      (node (ref "USB") (pin "14") (pinfunction "SH2_14") (pintype "passive+no_connect"))
    )
    (net (code "90") (name "unconnected-(USB-SH3-Pad15)") (class "Default")
      (node (ref "USB") (pin "15") (pinfunction "SH3_15") (pintype "passive+no_connect"))
    )
    (net (code "91") (name "unconnected-(USB-SH4-Pad16)") (class "Default")
      (node (ref "USB") (pin "16") (pinfunction "SH4_16") (pintype "passive+no_connect"))
    )
  )
)
